# LEVER-board-production-0_SENT_to_OSHPark.net
KiCad netlist of a schematic drawn in EAGLE
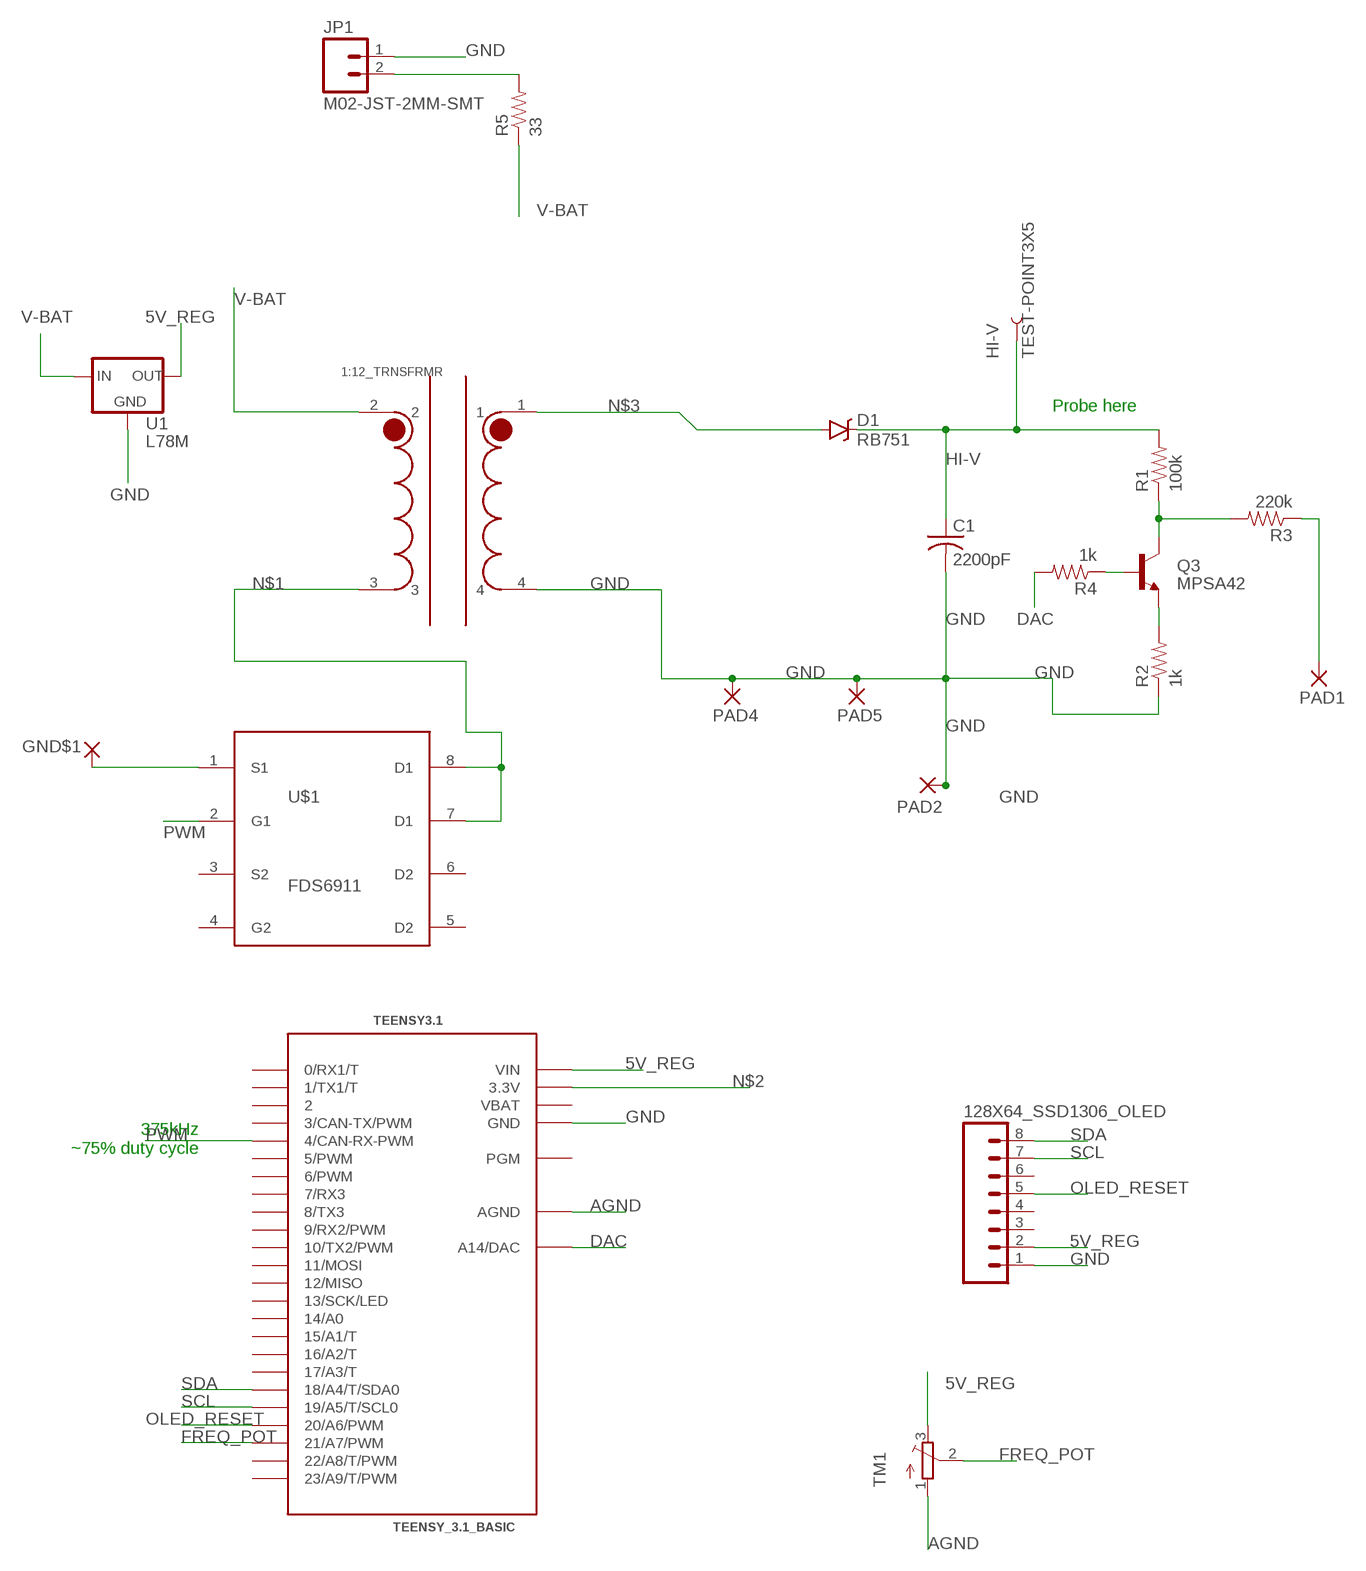
[diagram p0: schematic, sheet 1]

(export (version "E")
  (design (tool "Eeschema 10.0.6"))
  (components
    (comp (ref "1:12_TRNSFRMR")
      (value "PA0367")
      (footprint "eagle-import:PA0367")
      (libsource (lib "eagle-import") (part "PA0367"))
    )
    (comp (ref "128X64_SSD1306_OLED")
      (value "M08LOCK")
      (footprint "eagle-import:1X08_LOCK")
      (libsource (lib "eagle-import") (part "M08LOCK"))
    )
    (comp (ref "C1")
      (value "2200pF")
      (footprint "eagle-import:C1812")
      (libsource (lib "eagle-import") (part "C-USC1812"))
    )
    (comp (ref "D1")
      (value "RB751")
      (footprint "eagle-import:TO263")
      (libsource (lib "eagle-import") (part "QH03BZ600"))
    )
    (comp (ref "GND$1")
      (value "WIREPADSMD5-2,5")
      (footprint "eagle-import:5-2,5")
      (libsource (lib "eagle-import") (part "WIREPADSMD5-2,5"))
    )
    (comp (ref "HI-V")
      (value "TEST-POINT3X5")
      (footprint "eagle-import:PAD.03X.05")
      (libsource (lib "eagle-import") (part "TEST-POINT3X5"))
    )
    (comp (ref "JP1")
      (value "M02-JST-2MM-SMT")
      (footprint "eagle-import:JST-2-SMD")
      (libsource (lib "eagle-import") (part "M02-JST-2MM-SMT"))
    )
    (comp (ref "PAD1")
      (value "WIREPADSMD5-2,5")
      (footprint "eagle-import:5-2,5")
      (libsource (lib "eagle-import") (part "WIREPADSMD5-2,5"))
    )
    (comp (ref "PAD2")
      (value "WIREPADSMD5-2,5")
      (footprint "eagle-import:5-2,5")
      (libsource (lib "eagle-import") (part "WIREPADSMD5-2,5"))
    )
    (comp (ref "PAD4")
      (value "WIREPADSMD5-2,5")
      (footprint "eagle-import:5-2,5")
      (libsource (lib "eagle-import") (part "WIREPADSMD5-2,5"))
    )
    (comp (ref "PAD5")
      (value "WIREPADSMD5-2,5")
      (footprint "eagle-import:5-2,5")
      (libsource (lib "eagle-import") (part "WIREPADSMD5-2,5"))
    )
    (comp (ref "Q3")
      (value "MPSA42")
      (footprint "eagle-import:TO-92")
      (libsource (lib "eagle-import") (part "TRANSISTOR_NPNP2N2222A"))
    )
    (comp (ref "R1")
      (value "100k")
      (footprint "eagle-import:R2010")
      (libsource (lib "eagle-import") (part "RESISTOR2010"))
    )
    (comp (ref "R2")
      (value "1k")
      (footprint "eagle-import:1206")
      (libsource (lib "eagle-import") (part "RESISTOR1206"))
    )
    (comp (ref "R3")
      (value "220k")
      (footprint "eagle-import:R2010")
      (libsource (lib "eagle-import") (part "RESISTOR2010"))
    )
    (comp (ref "R4")
      (value "1k")
      (footprint "eagle-import:1206")
      (libsource (lib "eagle-import") (part "RESISTOR1206"))
    )
    (comp (ref "R5")
      (value "33")
      (footprint "eagle-import:1206")
      (libsource (lib "eagle-import") (part "RESISTOR1206"))
    )
    (comp (ref "TEENSY3.1")
      (value "TEENSY_3.1_BASIC")
      (footprint "eagle-import:TEENSY_3.1_BASIC")
      (libsource (lib "eagle-import") (part "TEENSY_3.1_BASIC"))
    )
    (comp (ref "TM1")
      (value "TRIMPOT3386")
      (footprint "eagle-import:TRIM-3386")
      (libsource (lib "eagle-import") (part "TRIMPOT3386"))
    )
    (comp (ref "U$1")
      (value "FDS6911")
      (footprint "eagle-import:SO8")
      (libsource (lib "eagle-import") (part "FDS6911"))
    )
    (comp (ref "U1")
      (value "L78M")
      (footprint "eagle-import:DPAK")
      (libsource (lib "eagle-import") (part "L78M"))
    )
  )
  (nets
    (net (code "1") (name "/5V_REG") (class "Default")
      (node (ref "128X64_SSD1306_OLED") (pin "2") (pinfunction "2_2") (pintype "passive"))
      (node (ref "TEENSY3.1") (pin "VIN") (pinfunction "VIN_VIN") (pintype "power_in"))
      (node (ref "TM1") (pin "3") (pinfunction "E_3") (pintype "passive"))
      (node (ref "U1") (pin "3") (pinfunction "OUT_3") (pintype "passive"))
    )
    (net (code "2") (name "/AGND") (class "Default")
      (node (ref "TEENSY3.1") (pin "AGND") (pinfunction "AGND_AGND") (pintype "power_in"))
      (node (ref "TM1") (pin "1") (pinfunction "A_1") (pintype "passive"))
    )
    (net (code "3") (name "/DAC") (class "Default")
      (node (ref "R4") (pin "2") (pinfunction "2_2") (pintype "passive"))
      (node (ref "TEENSY3.1") (pin "A14") (pinfunction "A14/DAC_A14") (pintype "bidirectional"))
    )
    (net (code "4") (name "/FREQ_POT") (class "Default")
      (node (ref "TEENSY3.1") (pin "21/A7") (pinfunction "21/A7/PWM_21/A7") (pintype "bidirectional"))
      (node (ref "TM1") (pin "2") (pinfunction "S_2") (pintype "passive"))
    )
    (net (code "5") (name "/GND") (class "Default")
      (node (ref "128X64_SSD1306_OLED") (pin "1") (pinfunction "1_1") (pintype "passive"))
      (node (ref "1:12_TRNSFRMR") (pin "4") (pinfunction "4_4") (pintype "bidirectional"))
      (node (ref "C1") (pin "2") (pinfunction "2_2") (pintype "passive"))
      (node (ref "GND$1") (pin "1") (pinfunction "P_1") (pintype "passive"))
      (node (ref "JP1") (pin "1") (pinfunction "2_1") (pintype "passive"))
      (node (ref "PAD2") (pin "1") (pinfunction "P_1") (pintype "passive"))
      (node (ref "PAD4") (pin "1") (pinfunction "P_1") (pintype "passive"))
      (node (ref "PAD5") (pin "1") (pinfunction "P_1") (pintype "passive"))
      (node (ref "R2") (pin "1") (pinfunction "1_1") (pintype "passive"))
      (node (ref "TEENSY3.1") (pin "GND") (pinfunction "GND_GND") (pintype "power_in"))
      (node (ref "TEENSY3.1") (pin "GND1") (pinfunction "GND_GND1") (pintype "power_in"))
      (node (ref "U$1") (pin "1") (pinfunction "S1_1") (pintype "bidirectional"))
      (node (ref "U1") (pin "4") (pinfunction "GND_4") (pintype "input"))
    )
    (net (code "6") (name "/HI-V") (class "Default")
      (node (ref "C1") (pin "1") (pinfunction "1_1") (pintype "passive"))
      (node (ref "D1") (pin "1") (pinfunction "C_1") (pintype "passive"))
      (node (ref "HI-V") (pin "P$1") (pinfunction "1_P$1") (pintype "bidirectional"))
      (node (ref "R1") (pin "2") (pinfunction "2_2") (pintype "passive"))
    )
    (net (code "7") (name "/N$1") (class "Default")
      (node (ref "1:12_TRNSFRMR") (pin "3") (pinfunction "3_3") (pintype "bidirectional"))
      (node (ref "U$1") (pin "7") (pinfunction "D1_7") (pintype "bidirectional"))
      (node (ref "U$1") (pin "8") (pinfunction "D1_8") (pintype "bidirectional"))
    )
    (net (code "8") (name "/N$2") (class "Default")
      (node (ref "TEENSY3.1") (pin "3.3V") (pinfunction "3.3V_3.3V") (pintype "power_in"))
      (node (ref "TEENSY3.1") (pin "3.3V1") (pinfunction "3.3V_3.3V1") (pintype "power_in"))
    )
    (net (code "9") (name "/N$3") (class "Default")
      (node (ref "1:12_TRNSFRMR") (pin "1") (pinfunction "1_1") (pintype "bidirectional"))
      (node (ref "D1") (pin "2") (pinfunction "A_2") (pintype "passive"))
    )
    (net (code "10") (name "/OLED_RESET") (class "Default")
      (node (ref "128X64_SSD1306_OLED") (pin "5") (pinfunction "5_5") (pintype "passive"))
      (node (ref "TEENSY3.1") (pin "20/A6") (pinfunction "20/A6/PWM_20/A6") (pintype "bidirectional"))
    )
    (net (code "11") (name "/PWM") (class "Default")
      (node (ref "TEENSY3.1") (pin "4") (pinfunction "4/CAN-RX-PWM_4") (pintype "bidirectional"))
      (node (ref "U$1") (pin "2") (pinfunction "G1_2") (pintype "bidirectional"))
    )
    (net (code "12") (name "/SCL") (class "Default")
      (node (ref "128X64_SSD1306_OLED") (pin "7") (pinfunction "7_7") (pintype "passive"))
      (node (ref "TEENSY3.1") (pin "19/A5") (pinfunction "19/A5/T/SCL0_19/A5") (pintype "bidirectional"))
    )
    (net (code "13") (name "/SDA") (class "Default")
      (node (ref "128X64_SSD1306_OLED") (pin "8") (pinfunction "8_8") (pintype "passive"))
      (node (ref "TEENSY3.1") (pin "18/A4") (pinfunction "18/A4/T/SDA0_18/A4") (pintype "bidirectional"))
    )
    (net (code "14") (name "/V-BAT") (class "Default")
      (node (ref "1:12_TRNSFRMR") (pin "2") (pinfunction "2_2") (pintype "bidirectional"))
      (node (ref "R5") (pin "1") (pinfunction "1_1") (pintype "passive"))
      (node (ref "U1") (pin "1") (pinfunction "IN_1") (pintype "input"))
    )
    (net (code "15") (name "/VBAT") (class "Default")
      (node (ref "TEENSY3.1") (pin "VBAT") (pinfunction "VBAT_VBAT") (pintype "power_in"))
    )
    (net (code "16") (name "Net-(JP1-1)") (class "Default")
      (node (ref "JP1") (pin "2") (pinfunction "1_2") (pintype "passive"))
      (node (ref "R5") (pin "2") (pinfunction "2_2") (pintype "passive"))
    )
    (net (code "17") (name "Net-(PAD1-P)") (class "Default")
      (node (ref "PAD1") (pin "1") (pinfunction "P_1") (pintype "passive"))
      (node (ref "R3") (pin "1") (pinfunction "1_1") (pintype "passive"))
    )
    (net (code "18") (name "Net-(Q3-B)") (class "Default")
      (node (ref "Q3") (pin "2") (pinfunction "B_2") (pintype "passive"))
      (node (ref "R4") (pin "1") (pinfunction "1_1") (pintype "passive"))
    )
    (net (code "19") (name "Net-(Q3-C)") (class "Default")
      (node (ref "Q3") (pin "1") (pinfunction "C_1") (pintype "passive"))
      (node (ref "R1") (pin "1") (pinfunction "1_1") (pintype "passive"))
      (node (ref "R3") (pin "2") (pinfunction "2_2") (pintype "passive"))
    )
    (net (code "20") (name "Net-(Q3-E)") (class "Default")
      (node (ref "Q3") (pin "3") (pinfunction "E_3") (pintype "passive"))
      (node (ref "R2") (pin "2") (pinfunction "2_2") (pintype "passive"))
    )
    (net (code "21") (name "unconnected-(128X64_SSD1306_OLED-Pad3)") (class "Default")
      (node (ref "128X64_SSD1306_OLED") (pin "3") (pinfunction "3_3") (pintype "passive"))
    )
    (net (code "22") (name "unconnected-(128X64_SSD1306_OLED-Pad4)") (class "Default")
      (node (ref "128X64_SSD1306_OLED") (pin "4") (pinfunction "4_4") (pintype "passive"))
    )
    (net (code "23") (name "unconnected-(128X64_SSD1306_OLED-Pad6)") (class "Default")
      (node (ref "128X64_SSD1306_OLED") (pin "6") (pinfunction "6_6") (pintype "passive"))
    )
    (net (code "24") (name "unconnected-(TEENSY3.1-0{slash}RX1{slash}T-Pad0)") (class "Default")
      (node (ref "TEENSY3.1") (pin "0") (pinfunction "0/RX1/T_0") (pintype "bidirectional"))
    )
    (net (code "25") (name "unconnected-(TEENSY3.1-1{slash}TX1{slash}T-Pad1)") (class "Default")
      (node (ref "TEENSY3.1") (pin "1") (pinfunction "1/TX1/T_1") (pintype "bidirectional"))
    )
    (net (code "26") (name "unconnected-(TEENSY3.1-3{slash}CAN-TX{slash}PWM-Pad3)") (class "Default")
      (node (ref "TEENSY3.1") (pin "3") (pinfunction "3/CAN-TX/PWM_3") (pintype "bidirectional"))
    )
    (net (code "27") (name "unconnected-(TEENSY3.1-5{slash}PWM-Pad5)") (class "Default")
      (node (ref "TEENSY3.1") (pin "5") (pinfunction "5/PWM_5") (pintype "bidirectional"))
    )
    (net (code "28") (name "unconnected-(TEENSY3.1-6{slash}PWM-Pad6)") (class "Default")
      (node (ref "TEENSY3.1") (pin "6") (pinfunction "6/PWM_6") (pintype "bidirectional"))
    )
    (net (code "29") (name "unconnected-(TEENSY3.1-7{slash}RX3-Pad7)") (class "Default")
      (node (ref "TEENSY3.1") (pin "7") (pinfunction "7/RX3_7") (pintype "bidirectional"))
    )
    (net (code "30") (name "unconnected-(TEENSY3.1-8{slash}TX3-Pad8)") (class "Default")
      (node (ref "TEENSY3.1") (pin "8") (pinfunction "8/TX3_8") (pintype "bidirectional"))
    )
    (net (code "31") (name "unconnected-(TEENSY3.1-9{slash}RX2{slash}PWM-Pad9)") (class "Default")
      (node (ref "TEENSY3.1") (pin "9") (pinfunction "9/RX2/PWM_9") (pintype "bidirectional"))
    )
    (net (code "32") (name "unconnected-(TEENSY3.1-10{slash}TX2{slash}PWM-Pad10)") (class "Default")
      (node (ref "TEENSY3.1") (pin "10") (pinfunction "10/TX2/PWM_10") (pintype "bidirectional"))
    )
    (net (code "33") (name "unconnected-(TEENSY3.1-11{slash}MOSI-Pad11)") (class "Default")
      (node (ref "TEENSY3.1") (pin "11") (pinfunction "11/MOSI_11") (pintype "bidirectional"))
    )
    (net (code "34") (name "unconnected-(TEENSY3.1-12{slash}MISO-Pad12)") (class "Default")
      (node (ref "TEENSY3.1") (pin "12") (pinfunction "12/MISO_12") (pintype "bidirectional"))
    )
    (net (code "35") (name "unconnected-(TEENSY3.1-13{slash}SCK{slash}LED-Pad13)") (class "Default")
      (node (ref "TEENSY3.1") (pin "13") (pinfunction "13/SCK/LED_13") (pintype "bidirectional"))
    )
    (net (code "36") (name "unconnected-(TEENSY3.1-15{slash}A1{slash}T-Pad15{slash}A1)") (class "Default")
      (node (ref "TEENSY3.1") (pin "15/A1") (pinfunction "15/A1/T_15/A1") (pintype "bidirectional"))
    )
    (net (code "37") (name "unconnected-(TEENSY3.1-16{slash}A2{slash}T-Pad16{slash}A2)") (class "Default")
      (node (ref "TEENSY3.1") (pin "16/A2") (pinfunction "16/A2/T_16/A2") (pintype "bidirectional"))
    )
    (net (code "38") (name "unconnected-(TEENSY3.1-17{slash}A3{slash}T-Pad17{slash}A3)") (class "Default")
      (node (ref "TEENSY3.1") (pin "17/A3") (pinfunction "17/A3/T_17/A3") (pintype "bidirectional"))
    )
    (net (code "39") (name "unconnected-(TEENSY3.1-22{slash}A8{slash}T{slash}PWM-Pad22{slash}A8)") (class "Default")
      (node (ref "TEENSY3.1") (pin "22/A8") (pinfunction "22/A8/T/PWM_22/A8") (pintype "bidirectional"))
    )
    (net (code "40") (name "unconnected-(TEENSY3.1-23{slash}A9{slash}T{slash}PWM-Pad23{slash}A9)") (class "Default")
      (node (ref "TEENSY3.1") (pin "23/A9") (pinfunction "23/A9/T/PWM_23/A9") (pintype "bidirectional"))
    )
    (net (code "41") (name "unconnected-(TEENSY3.1-Pad2)") (class "Default")
      (node (ref "TEENSY3.1") (pin "2") (pinfunction "2_2") (pintype "bidirectional"))
    )
    (net (code "42") (name "unconnected-(TEENSY3.1-Pad14{slash}A0)") (class "Default")
      (node (ref "TEENSY3.1") (pin "14/A0") (pinfunction "14/A0_14/A0") (pintype "bidirectional"))
    )
    (net (code "43") (name "unconnected-(TEENSY3.1-PadPGM)") (class "Default")
      (node (ref "TEENSY3.1") (pin "PGM") (pinfunction "PGM_PGM") (pintype "bidirectional"))
    )
    (net (code "44") (name "unconnected-(U$1-D2-Pad5)") (class "Default")
      (node (ref "U$1") (pin "5") (pinfunction "D2_5") (pintype "bidirectional"))
    )
    (net (code "45") (name "unconnected-(U$1-D2-Pad6)") (class "Default")
      (node (ref "U$1") (pin "6") (pinfunction "D2_6") (pintype "bidirectional"))
    )
    (net (code "46") (name "unconnected-(U$1-G2-Pad4)") (class "Default")
      (node (ref "U$1") (pin "4") (pinfunction "G2_4") (pintype "bidirectional"))
    )
    (net (code "47") (name "unconnected-(U$1-S2-Pad3)") (class "Default")
      (node (ref "U$1") (pin "3") (pinfunction "S2_3") (pintype "bidirectional"))
    )
  )
)
